# Power_Supply.net
KiCad netlist of a schematic drawn in Altium Designer
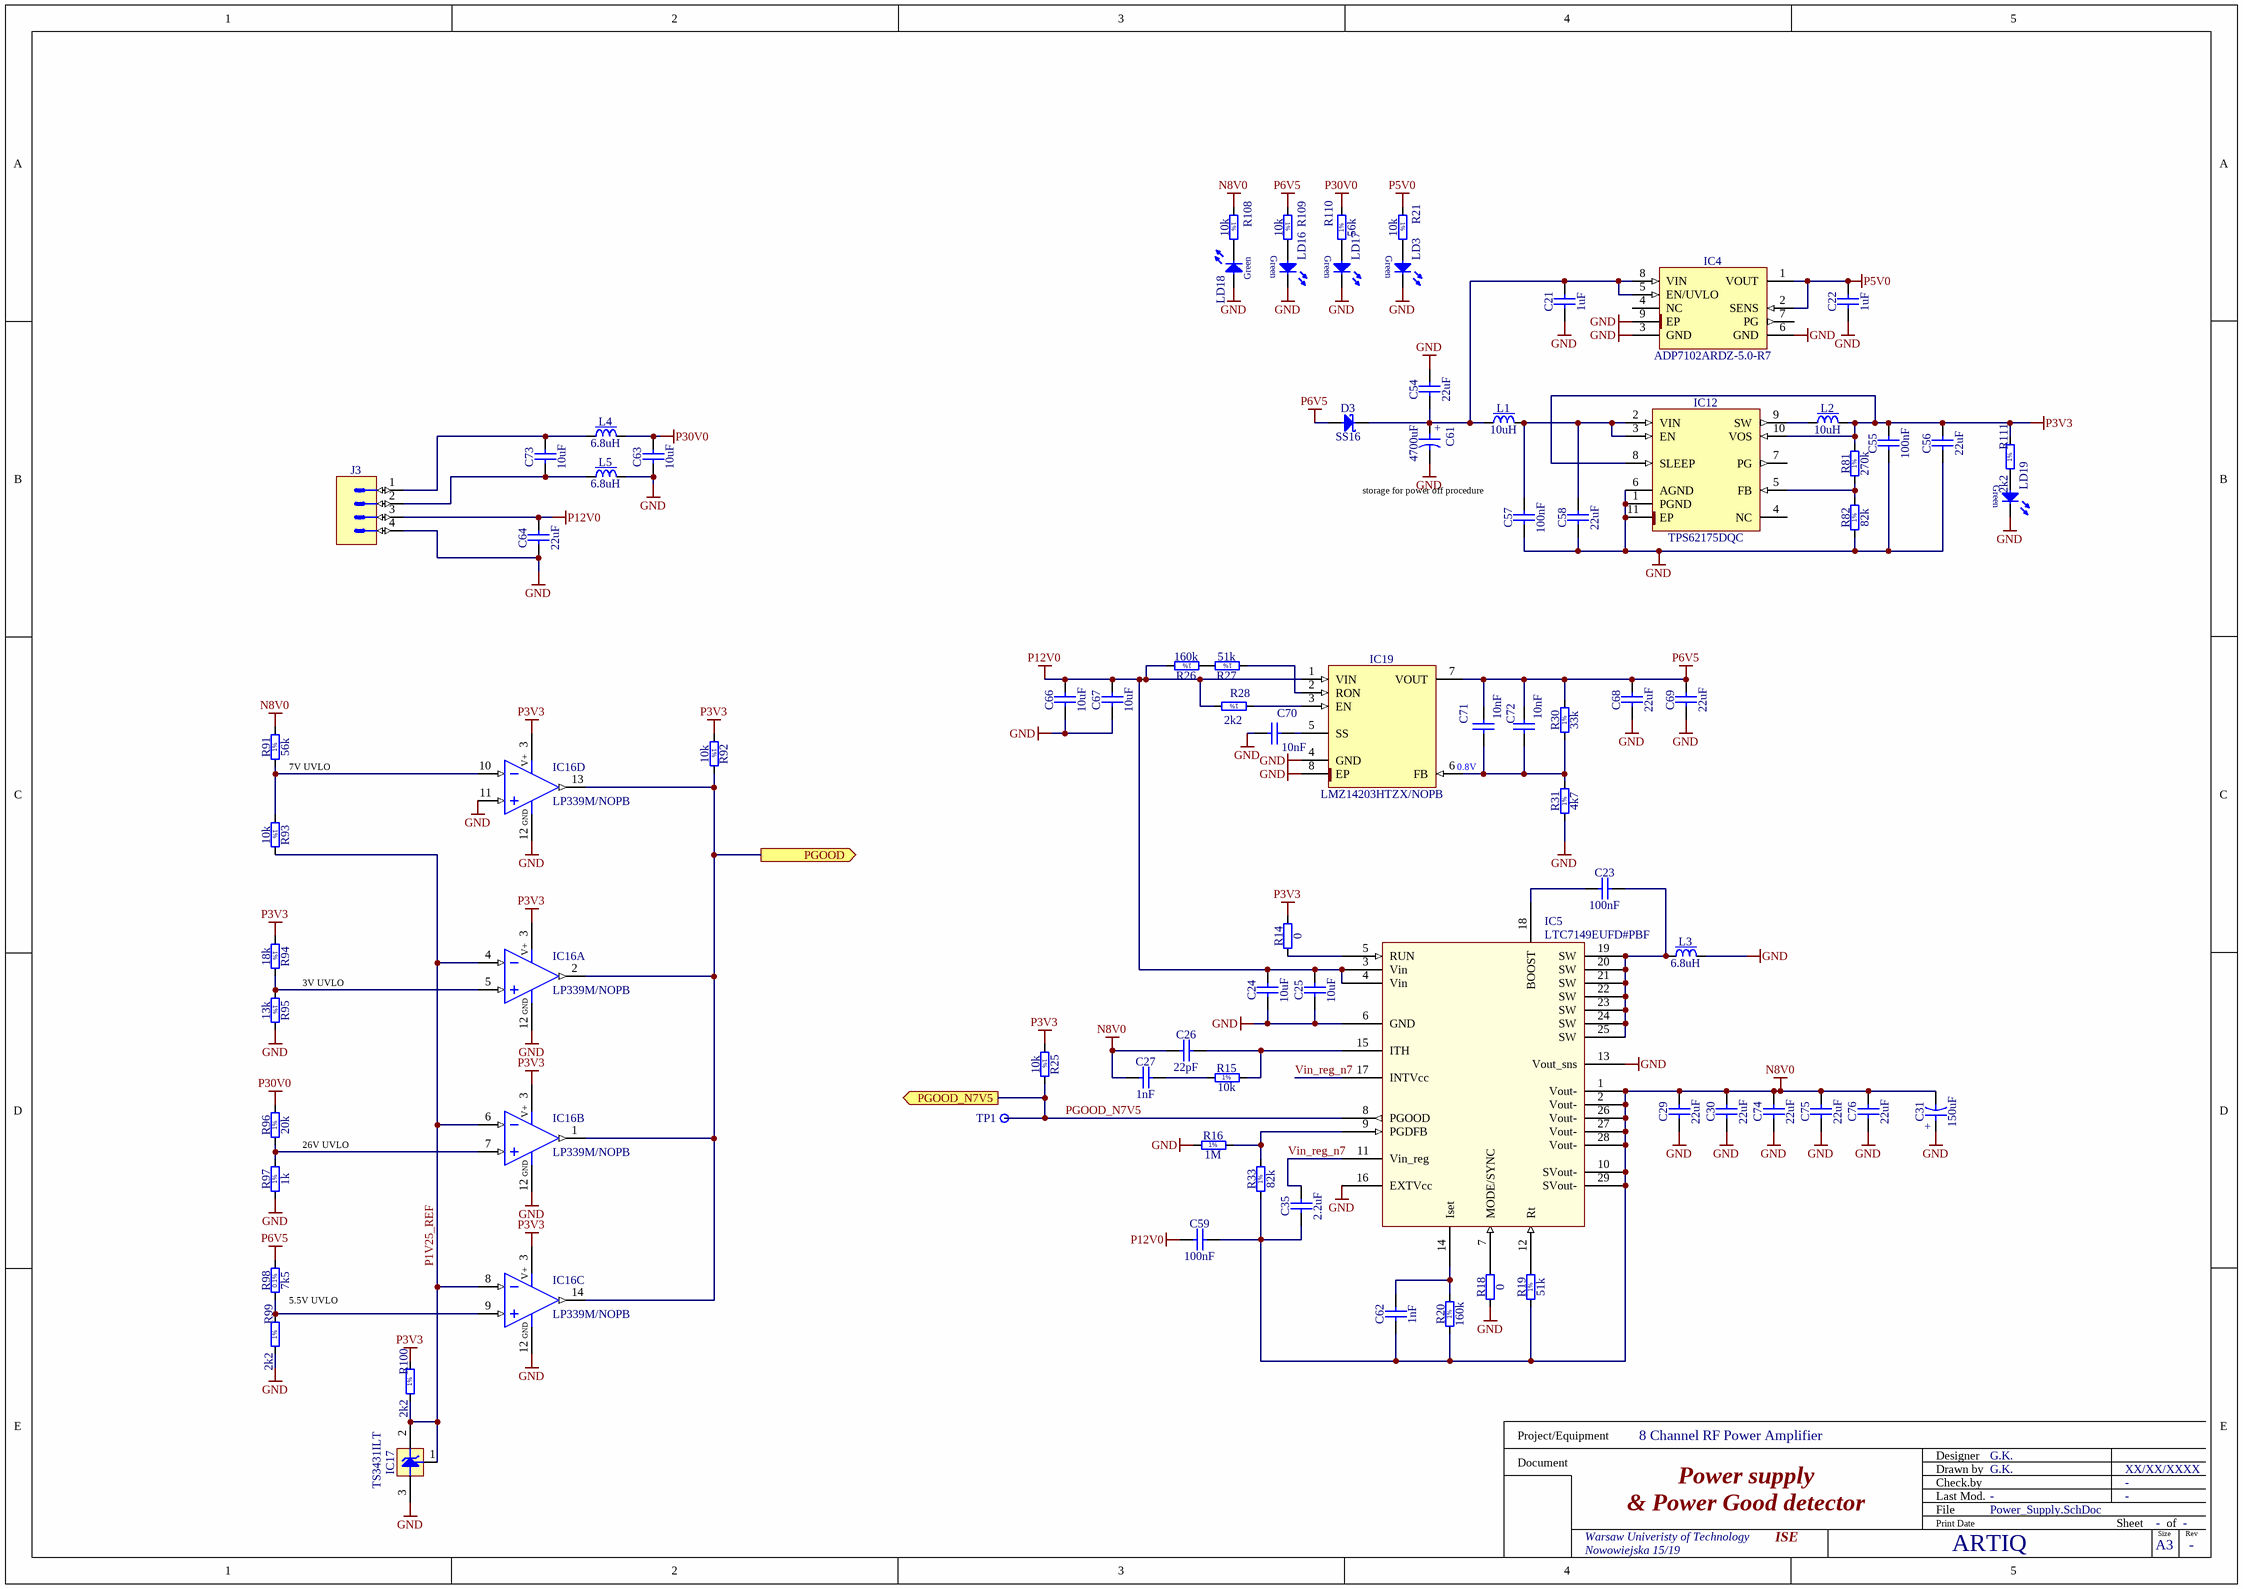
[diagram p0: Power_Supply.SchDoc]

(export (version "E")
  (design (tool "Eeschema 10.0.6"))
  (components
    (comp (ref "C21")
      (value "1uF")
      (footprint "CAPC2012X140N")
      (description "Non-polarised capacitor")
      (fields
        (field (name "PART NUMBER") "CC0805_1UF_35V_20%_X7R")
        (field (name "VOLTAGE") "35V")
        (field (name "AUTHOR") "CERN DEM JLC")
      )
      (libsource (lib "Capacitors") (part "Capacitor - non polarized"))
    )
    (comp (ref "C22")
      (value "1uF")
      (footprint "CAPC2012X140N")
      (description "Non-polarised capacitor")
      (fields
        (field (name "PART NUMBER") "CC0805_1UF_35V_20%_X7R")
        (field (name "VOLTAGE") "35V")
        (field (name "AUTHOR") "CERN DEM JLC")
      )
      (libsource (lib "Capacitors") (part "Capacitor - non polarized"))
    )
    (comp (ref "C23")
      (value "100nF")
      (footprint "CAPC1005X55N")
      (description "Non-polarised capacitor")
      (fields
        (field (name "PART NUMBER") "CC0402_100NF_16V_10%_X7R")
        (field (name "VOLTAGE") "16V")
        (field (name "AUTHOR") "CERN DEM JLC")
      )
      (libsource (lib "Capacitors") (part "Capacitor - non polarized"))
    )
    (comp (ref "C24")
      (value "10uF")
      (footprint "CAPC3216X190N")
      (description "Non-polarised capacitor")
      (fields
        (field (name "PART NUMBER") "CC1206_10UF_50V_10%_X5R_TDK_CGA5L3X5R1H106K160AB")
        (field (name "VOLTAGE") "50V")
        (field (name "AUTHOR") "CERN DEM BC")
      )
      (libsource (lib "Capacitors") (part "Capacitor - non polarized"))
    )
    (comp (ref "C25")
      (value "10uF")
      (footprint "CAPC3216X190N")
      (description "Non-polarised capacitor")
      (fields
        (field (name "PART NUMBER") "CC1206_10UF_50V_10%_X5R_TDK_CGA5L3X5R1H106K160AB")
        (field (name "VOLTAGE") "50V")
        (field (name "AUTHOR") "CERN DEM BC")
      )
      (libsource (lib "Capacitors") (part "Capacitor - non polarized"))
    )
    (comp (ref "C26")
      (value "22pF")
      (footprint "CAPC1005X55N")
      (description "Non-polarised capacitor")
      (fields
        (field (name "PART NUMBER") "CC0402_22PF_50V_5%_C0G")
        (field (name "VOLTAGE") "50V")
        (field (name "AUTHOR") "CERN DEM JLC")
      )
      (libsource (lib "Capacitors") (part "Capacitor - non polarized"))
    )
    (comp (ref "C27")
      (value "1nF")
      (footprint "CAPC1005X55N")
      (description "Non-polarised capacitor")
      (fields
        (field (name "PART NUMBER") "CC0402_1NF_50V_10%_X7R")
        (field (name "VOLTAGE") "50V")
        (field (name "AUTHOR") "CERN DEM JLC")
      )
      (libsource (lib "Capacitors") (part "Capacitor - non polarized"))
    )
    (comp (ref "C29")
      (value "22uF")
      (footprint "CAPC3216X180N")
      (description "Non-polarised capacitor")
      (fields
        (field (name "PART NUMBER") "CC1206_22UF_10V_10%_X7R")
        (field (name "VOLTAGE") "10V")
        (field (name "AUTHOR") "CERN DEM JLC")
      )
      (libsource (lib "Capacitors") (part "Capacitor - non polarized"))
    )
    (comp (ref "C30")
      (value "22uF")
      (footprint "CAPC3216X180N")
      (description "Non-polarised capacitor")
      (fields
        (field (name "PART NUMBER") "CC1206_22UF_10V_10%_X7R")
        (field (name "VOLTAGE") "10V")
        (field (name "AUTHOR") "CERN DEM JLC")
      )
      (libsource (lib "Capacitors") (part "Capacitor - non polarized"))
    )
    (comp (ref "C31")
      (value "150uF")
      (footprint "CAPMP7343X310N")
      (description "Polarised capacitor")
      (fields
        (field (name "PART NUMBER") "CTE7343-31_150UF_16V_10%_LESR0100")
        (field (name "VOLTAGE") "16V")
        (field (name "AUTHOR") "CERN DEM JLC")
      )
      (libsource (lib "Capacitors") (part "Capacitor - polarized"))
    )
    (comp (ref "C35")
      (value "2.2uF")
      (footprint "CAPC1608X87N")
      (description "Non-polarised capacitor")
      (fields
        (field (name "PART NUMBER") "CC0603_2.2UF_16V_10%_X5R")
        (field (name "VOLTAGE") "16V")
        (field (name "AUTHOR") "CERN DEM JLC")
      )
      (libsource (lib "Capacitors") (part "Capacitor - non polarized"))
    )
    (comp (ref "C54")
      (value "22uF")
      (footprint "CAPC2012X135N")
      (description "Non-polarised capacitor")
      (fields
        (field (name "PART NUMBER") "CC0805_22UF_16V_10%_X5R")
        (field (name "VOLTAGE") "16V")
        (field (name "AUTHOR") "CERN DEM JLC")
      )
      (libsource (lib "Capacitors") (part "Capacitor - non polarized"))
    )
    (comp (ref "C55")
      (value "100nF")
      (footprint "CAPC1005X55N")
      (description "Non-polarised capacitor")
      (fields
        (field (name "PART NUMBER") "CC0402_100NF_16V_10%_X5R")
        (field (name "VOLTAGE") "16V")
        (field (name "AUTHOR") "CERN DEM JLC")
      )
      (libsource (lib "Capacitors") (part "Capacitor - non polarized"))
    )
    (comp (ref "C56")
      (value "22uF")
      (footprint "CAPC2012X135N")
      (description "Non-polarised capacitor")
      (fields
        (field (name "PART NUMBER") "CC0805_22UF_16V_10%_X5R")
        (field (name "VOLTAGE") "16V")
        (field (name "AUTHOR") "CERN DEM JLC")
      )
      (libsource (lib "Capacitors") (part "Capacitor - non polarized"))
    )
    (comp (ref "C57")
      (value "100nF")
      (footprint "CAPC1005X55N")
      (description "Non-polarised capacitor")
      (fields
        (field (name "PART NUMBER") "CC0402_100NF_16V_10%_X5R")
        (field (name "VOLTAGE") "16V")
        (field (name "AUTHOR") "CERN DEM JLC")
      )
      (libsource (lib "Capacitors") (part "Capacitor - non polarized"))
    )
    (comp (ref "C58")
      (value "22uF")
      (footprint "CAPC2012X135N")
      (description "Non-polarised capacitor")
      (fields
        (field (name "PART NUMBER") "CC0805_22UF_16V_10%_X5R")
        (field (name "VOLTAGE") "16V")
        (field (name "AUTHOR") "CERN DEM JLC")
      )
      (libsource (lib "Capacitors") (part "Capacitor - non polarized"))
    )
    (comp (ref "C59")
      (value "100nF")
      (footprint "CAPC1608X87N")
      (description "Non-polarised capacitor")
      (fields
        (field (name "PART NUMBER") "CC0603_100NF_50V_10%_X5R")
        (field (name "VOLTAGE") "50V")
        (field (name "AUTHOR") "CERN DEM MR")
      )
      (libsource (lib "Capacitors") (part "Capacitor - non polarized"))
    )
    (comp (ref "C61")
      (value "4700uF")
      (footprint "CAPAE1900X1680N")
      (description "Polarised capacitor")
      (fields
        (field (name "PART NUMBER") "CAE1900-1680_4700UF_16V_20%")
        (field (name "VOLTAGE") "16V")
        (field (name "AUTHOR") "CERN DEM JLC")
      )
      (libsource (lib "Capacitors") (part "Capacitor - polarized"))
    )
    (comp (ref "C62")
      (value "1nF")
      (footprint "CAPC1005X55N")
      (description "Non-polarised capacitor")
      (fields
        (field (name "PART NUMBER") "CC0402_1NF_50V_10%_X7R")
        (field (name "VOLTAGE") "50V")
        (field (name "AUTHOR") "CERN DEM JLC")
      )
      (libsource (lib "Capacitors") (part "Capacitor - non polarized"))
    )
    (comp (ref "C63")
      (value "10uF")
      (footprint "CAPC3216X190N")
      (description "Non-polarised capacitor")
      (fields
        (field (name "PART NUMBER") "CC1206_10UF_50V_10%_X5R_TDK_CGA5L3X5R1H106K160AB")
        (field (name "VOLTAGE") "50V")
        (field (name "AUTHOR") "CERN DEM BC")
      )
      (libsource (lib "Capacitors") (part "Capacitor - non polarized"))
    )
    (comp (ref "C64")
      (value "22uF")
      (footprint "CAPC2012X135N")
      (description "Non-polarised capacitor")
      (fields
        (field (name "PART NUMBER") "CC0805_22UF_16V_10%_X5R")
        (field (name "VOLTAGE") "16V")
        (field (name "AUTHOR") "CERN DEM JLC")
      )
      (libsource (lib "Capacitors") (part "Capacitor - non polarized"))
    )
    (comp (ref "C66")
      (value "10uF")
      (footprint "CAPC3216X190N")
      (description "Non-polarised capacitor")
      (fields
        (field (name "PART NUMBER") "CC1206_10UF_50V_10%_X5R_TDK_CGA5L3X5R1H106K160AB")
        (field (name "VOLTAGE") "50V")
        (field (name "AUTHOR") "CERN DEM BC")
      )
      (libsource (lib "Capacitors") (part "Capacitor - non polarized"))
    )
    (comp (ref "C67")
      (value "10uF")
      (footprint "CAPC3216X190N")
      (description "Non-polarised capacitor")
      (fields
        (field (name "PART NUMBER") "CC1206_10UF_50V_10%_X5R_TDK_CGA5L3X5R1H106K160AB")
        (field (name "VOLTAGE") "50V")
        (field (name "AUTHOR") "CERN DEM BC")
      )
      (libsource (lib "Capacitors") (part "Capacitor - non polarized"))
    )
    (comp (ref "C68")
      (value "22uF")
      (footprint "CAPC2012X135N")
      (description "Non-polarised capacitor")
      (fields
        (field (name "PART NUMBER") "CC0805_22UF_16V_10%_X5R")
        (field (name "VOLTAGE") "16V")
        (field (name "AUTHOR") "CERN DEM JLC")
      )
      (libsource (lib "Capacitors") (part "Capacitor - non polarized"))
    )
    (comp (ref "C69")
      (value "22uF")
      (footprint "CAPC2012X135N")
      (description "Non-polarised capacitor")
      (fields
        (field (name "PART NUMBER") "CC0805_22UF_16V_10%_X5R")
        (field (name "VOLTAGE") "16V")
        (field (name "AUTHOR") "CERN DEM JLC")
      )
      (libsource (lib "Capacitors") (part "Capacitor - non polarized"))
    )
    (comp (ref "C70")
      (value "10nF")
      (footprint "CAPC1608X87N")
      (description "Non-polarised capacitor")
      (fields
        (field (name "PART NUMBER") "CC0603_10NF_50V_5%_C0G")
        (field (name "VOLTAGE") "50V")
        (field (name "AUTHOR") "CERN DEM JLC")
      )
      (libsource (lib "Capacitors") (part "Capacitor - non polarized"))
    )
    (comp (ref "C71")
      (value "10nF")
      (footprint "CAPC1608X87N")
      (description "Non-polarised capacitor")
      (fields
        (field (name "PART NUMBER") "CC0603_10NF_50V_5%_C0G")
        (field (name "VOLTAGE") "50V")
        (field (name "AUTHOR") "CERN DEM JLC")
      )
      (libsource (lib "Capacitors") (part "Capacitor - non polarized"))
    )
    (comp (ref "C72")
      (value "10nF")
      (footprint "CAPC1608X87N")
      (description "Non-polarised capacitor")
      (fields
        (field (name "PART NUMBER") "CC0603_10NF_50V_5%_C0G")
        (field (name "VOLTAGE") "50V")
        (field (name "AUTHOR") "CERN DEM JLC")
      )
      (libsource (lib "Capacitors") (part "Capacitor - non polarized"))
    )
    (comp (ref "C73")
      (value "10uF")
      (footprint "CAPC3216X190N")
      (description "Non-polarised capacitor")
      (fields
        (field (name "PART NUMBER") "CC1206_10UF_50V_10%_X5R_TDK_CGA5L3X5R1H106K160AB")
        (field (name "VOLTAGE") "50V")
        (field (name "AUTHOR") "CERN DEM BC")
      )
      (libsource (lib "Capacitors") (part "Capacitor - non polarized"))
    )
    (comp (ref "C74")
      (value "22uF")
      (footprint "CAPC3216X180N")
      (description "Non-polarised capacitor")
      (fields
        (field (name "PART NUMBER") "CC1206_22UF_10V_10%_X7R")
        (field (name "VOLTAGE") "10V")
        (field (name "AUTHOR") "CERN DEM JLC")
      )
      (libsource (lib "Capacitors") (part "Capacitor - non polarized"))
    )
    (comp (ref "C75")
      (value "22uF")
      (footprint "CAPC3216X180N")
      (description "Non-polarised capacitor")
      (fields
        (field (name "PART NUMBER") "CC1206_22UF_10V_10%_X7R")
        (field (name "VOLTAGE") "10V")
        (field (name "AUTHOR") "CERN DEM JLC")
      )
      (libsource (lib "Capacitors") (part "Capacitor - non polarized"))
    )
    (comp (ref "C76")
      (value "22uF")
      (footprint "CAPC3216X180N")
      (description "Non-polarised capacitor")
      (fields
        (field (name "PART NUMBER") "CC1206_22UF_10V_10%_X7R")
        (field (name "VOLTAGE") "10V")
        (field (name "AUTHOR") "CERN DEM JLC")
      )
      (libsource (lib "Capacitors") (part "Capacitor - non polarized"))
    )
    (comp (ref "D3")
      (value "SS16")
      (footprint "DIOM5127X229N")
      (description "Schottky Diode")
      (fields
        (field (name "VOLTAGE") "60V")
        (field (name "POWER") "1A")
        (field (name "AUTHOR") "CERN DEM JLC")
      )
      (libsource (lib "ICs And Semiconductors") (part "Diode Schottky"))
    )
    (comp (ref "IC4")
      (value "ADP7102ARDZ-5.0-R7")
      (footprint "SOIC127P600X175-9N-R241X309")
      (description "300 mA, Low Noise, CMOS LDO Linear Regulator")
      (fields (field (name "MANUFACTURER") "ANALOG DEVICES") (field (name "AUTHOR") "CERN DEM JLC"))
      (libsource (lib "ICs And Semiconductors") (part "ADP7102ARDZ-X.X-R7"))
    )
    (comp (ref "IC5")
      (value "LTC7149EUFD#PBF")
      (footprint "QFN50P400X500X80_HS-29N")
      (description "LTC7149 - 60V, 4A Synchronous Step-Down Regulator for Inverting Outputs")
      (fields (field (name "MANUFACTURER") "Linear technology"))
      (libsource (lib "misc") (part "LTC7149EUFD#PBF"))
    )
    (comp (ref "IC12")
      (value "TPS62175DQC")
      (footprint "SON50P200X300X80-11N-R94X250")
      (description "4.75-28VDC to 1-6VDC, 500mA Step-Down Converter With Sleep Mode")
      (fields (field (name "MANUFACTURER") "TEXAS INSTRUMENTS") (field (name "AUTHOR") "CERN DEM JMW"))
      (libsource (lib "ICs And Semiconductors") (part "TPS62175"))
    )
    (comp (ref "IC16")
      (value "LP339M/NOPB")
      (footprint "SOIC127P600X175-14N")
      (description "Quad Operational Amplifier")
      (fields (field (name "MANUFACTURER") "TEXAS INSTRUMENTS") (field (name "AUTHOR") "CERN DEM MR"))
      (libsource (lib "ICs And Semiconductors") (part "Operational Amplifier x4 Type5"))
    )
    (comp (ref "IC17")
      (value "TS3431ILT")
      (footprint "SOT95P237X112-3N")
      (description "Precision Reference 1=Adj 2=Cathode 3=Anode")
      (fields (field (name "MANUFACTURER") "ST MICROELECTRONICS") (field (name "AUTHOR") "CERN DEM JLC"))
      (libsource (lib "ICs And Semiconductors") (part "VREF 1ADJ-2C-3A"))
    )
    (comp (ref "IC19")
      (value "LMZ14203HTZX/NOPB")
      (footprint "TEXAS_TO-PMOD (NDW)")
      (description "3A SIMPLE SWITCHER® Power Module with 42V Maximum Input Voltage")
      (fields (field (name "MANUFACTURER") "TEXAS INSTRUMENTS") (field (name "AUTHOR") "GK"))
      (libsource (lib "LIBRARY_SCH") (part "PM_LMZ14203"))
    )
    (comp (ref "J3")
      (value "~")
      (footprint "PHOENIX_1755752")
      (description "Connector 4 Male")
      (fields
        (field (name "PART NUMBER") "PHOENIX_1755752")
        (field (name "MANUFACTURER") "PHOENIX CONTACT")
        (field (name "AUTHOR") "CERN DEM JLC")
      )
      (libsource (lib "Connectors") (part "Connector 4 Male"))
    )
    (comp (ref "L1")
      (value "10uH")
      (footprint "IND_MURATA-PS_8400")
      (description "Inductor With Core")
      (fields
        (field (name "PART NUMBER") "IND_10UH_10%_MURATA-PS_8400")
        (field (name "POWER") "950mA")
        (field (name "AUTHOR") "CERN DEM JLC")
      )
      (libsource (lib "Inductors & Transformers") (part "Inductor With Magnetic core"))
    )
    (comp (ref "L2")
      (value "10uH")
      (footprint "IND_MURATA-PS_8400")
      (description "Inductor With Core")
      (fields
        (field (name "PART NUMBER") "IND_10UH_10%_MURATA-PS_8400")
        (field (name "POWER") "950mA")
        (field (name "AUTHOR") "CERN DEM JLC")
      )
      (libsource (lib "Inductors & Transformers") (part "Inductor With Magnetic core"))
    )
    (comp (ref "L3")
      (value "6.8uH")
      (footprint "INDM6965X300N")
      (description "Inductor With Core")
      (fields
        (field (name "PART NUMBER") "IND2525_1.5UH_20%_VISHAY_IHLP-2525CZ")
        (field (name "POWER") "9A")
        (field (name "AUTHOR") "CERN DEM JLC")
      )
      (libsource (lib "Inductors & Transformers") (part "Inductor With Magnetic core"))
    )
    (comp (ref "L4")
      (value "6.8uH")
      (footprint "INDM6965X300N")
      (description "Inductor With Core")
      (fields
        (field (name "PART NUMBER") "IND2525_1.5UH_20%_VISHAY_IHLP-2525CZ")
        (field (name "POWER") "9A")
        (field (name "AUTHOR") "CERN DEM JLC")
      )
      (libsource (lib "Inductors & Transformers") (part "Inductor With Magnetic core"))
    )
    (comp (ref "L5")
      (value "6.8uH")
      (footprint "INDM6965X300N")
      (description "Inductor With Core")
      (fields
        (field (name "PART NUMBER") "IND2525_1.5UH_20%_VISHAY_IHLP-2525CZ")
        (field (name "POWER") "9A")
        (field (name "AUTHOR") "CERN DEM JLC")
      )
      (libsource (lib "Inductors & Transformers") (part "Inductor With Magnetic core"))
    )
    (comp (ref "LD3")
      (value "Green")
      (footprint "LED_KINGBRIGHT_KPH-1608CGCK")
      (description "LED Green 1C 2A")
      (fields
        (field (name "PART NUMBER") "LED_KINGBRIGHT_KPH-1608CGCK")
        (field (name "MANUFACTURER") "KINGBRIGHT")
        (field (name "AUTHOR") "CERN DEM JLC")
      )
      (libsource (lib "ICs And Semiconductors") (part "LED Green 1C 2A"))
    )
    (comp (ref "LD16")
      (value "Green")
      (footprint "LED_KINGBRIGHT_KPH-1608CGCK")
      (description "LED Green 1C 2A")
      (fields
        (field (name "PART NUMBER") "LED_KINGBRIGHT_KPH-1608CGCK")
        (field (name "MANUFACTURER") "KINGBRIGHT")
        (field (name "AUTHOR") "CERN DEM JLC")
      )
      (libsource (lib "ICs And Semiconductors") (part "LED Green 1C 2A"))
    )
    (comp (ref "LD17")
      (value "Green")
      (footprint "LED_KINGBRIGHT_KPH-1608CGCK")
      (description "LED Green 1C 2A")
      (fields
        (field (name "PART NUMBER") "LED_KINGBRIGHT_KPH-1608CGCK")
        (field (name "MANUFACTURER") "KINGBRIGHT")
        (field (name "AUTHOR") "CERN DEM JLC")
      )
      (libsource (lib "ICs And Semiconductors") (part "LED Green 1C 2A"))
    )
    (comp (ref "LD18")
      (value "Green")
      (footprint "LED_KINGBRIGHT_KPH-1608CGCK")
      (description "LED Green 1C 2A")
      (fields
        (field (name "PART NUMBER") "LED_KINGBRIGHT_KPH-1608CGCK")
        (field (name "MANUFACTURER") "KINGBRIGHT")
        (field (name "AUTHOR") "CERN DEM JLC")
      )
      (libsource (lib "ICs And Semiconductors") (part "LED Green 1C 2A"))
    )
    (comp (ref "LD19")
      (value "Green")
      (footprint "LED_OSRAM_LGL29K")
      (description "LED Green 1C 2A")
      (fields
        (field (name "PART NUMBER") "LED_OSRAM_LG L29K-G2J1-24-Z")
        (field (name "MANUFACTURER") "OSRAM")
        (field (name "AUTHOR") "CERN DEM JLC")
      )
      (libsource (lib "ICs And Semiconductors") (part "LED Green 1C 2A"))
    )
    (comp (ref "R14")
      (value "0")
      (footprint "RESC1005X40N")
      (description "Resistor")
      (fields
        (field (name "PART NUMBER") "R0402_0R_JUMPER")
        (field (name "MANUFACTURER") "GENERIC")
        (field (name "AUTHOR") "CERN DEM JLC")
      )
      (libsource (lib "Resistors") (part "Resistor"))
    )
    (comp (ref "R15")
      (value "10k")
      (footprint "RESC1005X40N")
      (description "Resistor - 1%")
      (fields
        (field (name "PART NUMBER") "R0402_10K_1%_0.0625W_100PPM")
        (field (name "POWER") "0.0625W")
        (field (name "AUTHOR") "CERN DEM JLC")
      )
      (libsource (lib "Resistors") (part "Resistor - 1%"))
    )
    (comp (ref "R16")
      (value "1M")
      (footprint "RESC1005X40N")
      (description "Resistor - 1%")
      (fields
        (field (name "PART NUMBER") "R0402_1M_1%_0.0625W_100PPM")
        (field (name "POWER") "0.0625W")
        (field (name "AUTHOR") "CERN DEM JLC")
      )
      (libsource (lib "Resistors") (part "Resistor - 1%"))
    )
    (comp (ref "R18")
      (value "0")
      (footprint "RESC1005X40N")
      (description "Resistor")
      (fields
        (field (name "PART NUMBER") "R0402_0R_JUMPER")
        (field (name "MANUFACTURER") "GENERIC")
        (field (name "AUTHOR") "CERN DEM JLC")
      )
      (libsource (lib "Resistors") (part "Resistor"))
    )
    (comp (ref "R19")
      (value "51k")
      (footprint "RESC1005X40N")
      (description "Resistor - 1%")
      (fields
        (field (name "PART NUMBER") "R0402_51K_1%_0.0625W_100PPM")
        (field (name "POWER") "0.0625W")
        (field (name "AUTHOR") "CERN DEM JLC")
      )
      (libsource (lib "Resistors") (part "Resistor - 1%"))
    )
    (comp (ref "R20")
      (value "160k")
      (footprint "RESC1005X40N")
      (description "Resistor - 1%")
      (fields
        (field (name "PART NUMBER") "R0402_160K_1%_0.0625W_100PPM")
        (field (name "POWER") "0.0625W")
        (field (name "AUTHOR") "CERN DEM JLC")
      )
      (libsource (lib "Resistors") (part "Resistor - 1%"))
    )
    (comp (ref "R21")
      (value "10k")
      (footprint "RESC1005X40N")
      (description "Resistor - 1%")
      (fields
        (field (name "PART NUMBER") "R0402_10K_1%_0.0625W_100PPM")
        (field (name "POWER") "0.0625W")
        (field (name "AUTHOR") "CERN DEM JLC")
      )
      (libsource (lib "Resistors") (part "Resistor - 1%"))
    )
    (comp (ref "R25")
      (value "10k")
      (footprint "RESC1005X40N")
      (description "Resistor - 1%")
      (fields
        (field (name "PART NUMBER") "R0402_10K_1%_0.0625W_100PPM")
        (field (name "POWER") "0.0625W")
        (field (name "AUTHOR") "CERN DEM JLC")
      )
      (libsource (lib "Resistors") (part "Resistor - 1%"))
    )
    (comp (ref "R26")
      (value "160k")
      (footprint "RESC1005X40N")
      (description "Resistor - 1%")
      (fields
        (field (name "PART NUMBER") "R0402_160K_1%_0.0625W_100PPM")
        (field (name "POWER") "0.0625W")
        (field (name "AUTHOR") "CERN DEM JLC")
      )
      (libsource (lib "Resistors") (part "Resistor - 1%"))
    )
    (comp (ref "R27")
      (value "51k")
      (footprint "RESC1005X40N")
      (description "Resistor - 1%")
      (fields
        (field (name "PART NUMBER") "R0402_51K_1%_0.0625W_100PPM")
        (field (name "POWER") "0.0625W")
        (field (name "AUTHOR") "CERN DEM JLC")
      )
      (libsource (lib "Resistors") (part "Resistor - 1%"))
    )
    (comp (ref "R28")
      (value "2k2")
      (footprint "RESC1005X40N")
      (description "Resistor - 1%")
      (fields
        (field (name "PART NUMBER") "R0402_2K2_1%_0.0625W_100PPM")
        (field (name "POWER") "0.0625W")
        (field (name "AUTHOR") "CERN DEM JLC")
      )
      (libsource (lib "Resistors") (part "Resistor - 1%"))
    )
    (comp (ref "R30")
      (value "33k")
      (footprint "RESC1608X55N")
      (description "Resistor - 1%")
      (fields
        (field (name "PART NUMBER") "R0603_33K_1%_0.1W_100PPM")
        (field (name "POWER") "0.1W")
        (field (name "AUTHOR") "CERN DEM JLC")
      )
      (libsource (lib "Resistors") (part "Resistor - 1%"))
    )
    (comp (ref "R31")
      (value "4k7")
      (footprint "RESC1608X55N")
      (description "Resistor - 1%")
      (fields
        (field (name "PART NUMBER") "R0603_4K7_1%_0.1W_100PPM")
        (field (name "POWER") "0.1W")
        (field (name "AUTHOR") "CERN DEM JLC")
      )
      (libsource (lib "Resistors") (part "Resistor - 1%"))
    )
    (comp (ref "R33")
      (value "82k")
      (footprint "RESC1608X55N")
      (description "Resistor - 1%")
      (fields
        (field (name "PART NUMBER") "R0603_82K_1%_0.1W_100PPM")
        (field (name "POWER") "0.1W")
        (field (name "AUTHOR") "CERN DEM JLC")
      )
      (libsource (lib "Resistors") (part "Resistor - 1%"))
    )
    (comp (ref "R81")
      (value "270k")
      (footprint "RESC1608X55N")
      (description "Resistor - 1%")
      (fields
        (field (name "PART NUMBER") "R0603_270K_1%_0.1W_100PPM")
        (field (name "POWER") "0.1W")
        (field (name "AUTHOR") "CERN DEM JLC")
      )
      (libsource (lib "Resistors") (part "Resistor - 1%"))
    )
    (comp (ref "R82")
      (value "82k")
      (footprint "RESC1608X55N")
      (description "Resistor - 1%")
      (fields
        (field (name "PART NUMBER") "R0603_82K_1%_0.1W_100PPM")
        (field (name "POWER") "0.1W")
        (field (name "AUTHOR") "CERN DEM JLC")
      )
      (libsource (lib "Resistors") (part "Resistor - 1%"))
    )
    (comp (ref "R91")
      (value "56k")
      (footprint "RESC1608X55N")
      (description "Resistor - 1%")
      (fields
        (field (name "PART NUMBER") "R0603_56K_1%_0.1W_100PPM")
        (field (name "POWER") "0.1W")
        (field (name "AUTHOR") "CERN DEM JLC")
      )
      (libsource (lib "Resistors") (part "Resistor - 1%"))
    )
    (comp (ref "R92")
      (value "10k")
      (footprint "RESC1005X40N")
      (description "Resistor - 1%")
      (fields
        (field (name "PART NUMBER") "R0402_10K_1%_0.0625W_100PPM")
        (field (name "POWER") "0.0625W")
        (field (name "AUTHOR") "CERN DEM JLC")
      )
      (libsource (lib "Resistors") (part "Resistor - 1%"))
    )
    (comp (ref "R93")
      (value "10k")
      (footprint "RESC1005X40N")
      (description "Resistor - 1%")
      (fields
        (field (name "PART NUMBER") "R0402_10K_1%_0.0625W_100PPM")
        (field (name "POWER") "0.0625W")
        (field (name "AUTHOR") "CERN DEM JLC")
      )
      (libsource (lib "Resistors") (part "Resistor - 1%"))
    )
    (comp (ref "R94")
      (value "18k")
      (footprint "RESC1608X55N")
      (description "Resistor - 1%")
      (fields
        (field (name "PART NUMBER") "R0603_18K_1%_0.1W_100PPM")
        (field (name "POWER") "0.1W")
        (field (name "AUTHOR") "CERN DEM JLC")
      )
      (libsource (lib "Resistors") (part "Resistor - 1%"))
    )
    (comp (ref "R95")
      (value "13k")
      (footprint "RESC1608X55N")
      (description "Resistor - 1%")
      (fields
        (field (name "PART NUMBER") "R0603_13K_1%_0.1W_100PPM")
        (field (name "POWER") "0.1W")
        (field (name "AUTHOR") "CERN DEM JLC")
      )
      (libsource (lib "Resistors") (part "Resistor - 1%"))
    )
    (comp (ref "R96")
      (value "20k")
      (footprint "RESC1608X55N")
      (description "Resistor - 1%")
      (fields
        (field (name "PART NUMBER") "R0603_20K_1%_0.1W_100PPM")
        (field (name "POWER") "0.1W")
        (field (name "AUTHOR") "CERN DEM JLC")
      )
      (libsource (lib "Resistors") (part "Resistor - 1%"))
    )
    (comp (ref "R97")
      (value "1k")
      (footprint "RESC1608X55N")
      (description "Resistor - 1%")
      (fields
        (field (name "PART NUMBER") "R0603_1K_1%_0.1W_100PPM")
        (field (name "POWER") "0.1W")
        (field (name "AUTHOR") "CERN DEM JLC")
      )
      (libsource (lib "Resistors") (part "Resistor - 1%"))
    )
    (comp (ref "R98")
      (value "7k5")
      (footprint "RESC1608X55N")
      (description "Resistor - 0.1%")
      (fields
        (field (name "PART NUMBER") "R0603_7K5_0.1%_0.063W_10PPM")
        (field (name "POWER") "0.063W")
        (field (name "AUTHOR") "CERN DEM JLC")
      )
      (libsource (lib "Resistors") (part "Resistor - 0.1%"))
    )
    (comp (ref "R99")
      (value "2k2")
      (footprint "RESC1005X40N")
      (description "Resistor - 1%")
      (fields
        (field (name "PART NUMBER") "R0402_2K2_1%_0.0625W_100PPM")
        (field (name "POWER") "0.0625W")
        (field (name "AUTHOR") "CERN DEM JLC")
      )
      (libsource (lib "Resistors") (part "Resistor - 1%"))
    )
    (comp (ref "R100")
      (value "2k2")
      (footprint "RESC1005X40N")
      (description "Resistor - 1%")
      (fields
        (field (name "PART NUMBER") "R0402_2K2_1%_0.0625W_100PPM")
        (field (name "POWER") "0.0625W")
        (field (name "AUTHOR") "CERN DEM JLC")
      )
      (libsource (lib "Resistors") (part "Resistor - 1%"))
    )
    (comp (ref "R108")
      (value "10k")
      (footprint "RESC1005X40N")
      (description "Resistor - 1%")
      (fields
        (field (name "PART NUMBER") "R0402_10K_1%_0.0625W_100PPM")
        (field (name "POWER") "0.0625W")
        (field (name "AUTHOR") "CERN DEM JLC")
      )
      (libsource (lib "Resistors") (part "Resistor - 1%"))
    )
    (comp (ref "R109")
      (value "10k")
      (footprint "RESC1005X40N")
      (description "Resistor - 1%")
      (fields
        (field (name "PART NUMBER") "R0402_10K_1%_0.0625W_100PPM")
        (field (name "POWER") "0.0625W")
        (field (name "AUTHOR") "CERN DEM JLC")
      )
      (libsource (lib "Resistors") (part "Resistor - 1%"))
    )
    (comp (ref "R110")
      (value "56k")
      (footprint "RESC1608X55N")
      (description "Resistor - 1%")
      (fields
        (field (name "PART NUMBER") "R0603_56K_1%_0.1W_100PPM")
        (field (name "POWER") "0.1W")
        (field (name "AUTHOR") "CERN DEM JLC")
      )
      (libsource (lib "Resistors") (part "Resistor - 1%"))
    )
    (comp (ref "R111")
      (value "2k2")
      (footprint "RESC1005X40N")
      (description "Resistor - 1%")
      (fields
        (field (name "PART NUMBER") "R0402_2K2_1%_0.0625W_100PPM")
        (field (name "POWER") "0.0625W")
        (field (name "AUTHOR") "CERN DEM JLC")
      )
      (libsource (lib "Resistors") (part "Resistor - 1%"))
    )
    (comp (ref "TP1")
      (value "Test Point")
      (footprint "TPS127")
      (fields (field (name "PART NUMBER") "SMD_PAD_1.27X1.27MM") (field (name "AUTHOR") "CERN DEM JLC"))
      (libsource (lib "Eletro-mechanical") (part "Test Point"))
    )
  )
  (nets
    (net (code "1") (name "/P1V25_REF") (class "Default")
      (node (ref "IC16") (pin "4") (pinfunction "IN-_4") (pintype "input"))
      (node (ref "IC16") (pin "6") (pinfunction "IN-_6") (pintype "input"))
      (node (ref "IC16") (pin "8") (pinfunction "IN-_8") (pintype "input"))
      (node (ref "IC17") (pin "1") (pinfunction "Adj_1") (pintype "passive"))
      (node (ref "IC17") (pin "2") (pinfunction "C_2") (pintype "passive"))
      (node (ref "R100") (pin "1") (pinfunction "1_1") (pintype "passive"))
      (node (ref "R93") (pin "2") (pinfunction "2_2") (pintype "passive"))
    )
    (net (code "2") (name "/PGOOD") (class "Default")
      (node (ref "IC16") (pin "1") (pinfunction "OUT_1") (pintype "output"))
      (node (ref "IC16") (pin "13") (pinfunction "OUT_13") (pintype "output"))
      (node (ref "IC16") (pin "14") (pinfunction "OUT_14") (pintype "output"))
      (node (ref "IC16") (pin "2") (pinfunction "OUT_2") (pintype "output"))
      (node (ref "R92") (pin "2") (pinfunction "2_2") (pintype "passive"))
    )
    (net (code "3") (name "/PGOOD_N7V5") (class "Default")
      (node (ref "IC5") (pin "8") (pinfunction "PGOOD_8") (pintype "output"))
      (node (ref "R25") (pin "2") (pinfunction "2_2") (pintype "passive"))
      (node (ref "TP1") (pin "1") (pinfunction "1_1") (pintype "bidirectional"))
    )
    (net (code "4") (name "/Vin_reg_n7") (class "Default")
      (node (ref "C35") (pin "2") (pinfunction "2_2") (pintype "passive"))
      (node (ref "IC5") (pin "11") (pinfunction "Vin_reg_11") (pintype "passive"))
      (node (ref "IC5") (pin "17") (pinfunction "INTVcc_17") (pintype "power_in"))
    )
    (net (code "5") (name "GND") (class "Default")
      (node (ref "C21") (pin "1") (pinfunction "1_1") (pintype "passive"))
      (node (ref "C22") (pin "1") (pinfunction "1_1") (pintype "passive"))
      (node (ref "C24") (pin "1") (pinfunction "1_1") (pintype "passive"))
      (node (ref "C25") (pin "1") (pinfunction "1_1") (pintype "passive"))
      (node (ref "C29") (pin "1") (pinfunction "1_1") (pintype "passive"))
      (node (ref "C30") (pin "1") (pinfunction "1_1") (pintype "passive"))
      (node (ref "C31") (pin "1") (pinfunction "1_1") (pintype "passive"))
      (node (ref "C54") (pin "2") (pinfunction "2_2") (pintype "passive"))
      (node (ref "C55") (pin "1") (pinfunction "1_1") (pintype "passive"))
      (node (ref "C56") (pin "1") (pinfunction "1_1") (pintype "passive"))
      (node (ref "C57") (pin "1") (pinfunction "1_1") (pintype "passive"))
      (node (ref "C58") (pin "1") (pinfunction "1_1") (pintype "passive"))
      (node (ref "C61") (pin "2") (pinfunction "2_2") (pintype "passive"))
      (node (ref "C63") (pin "1") (pinfunction "1_1") (pintype "passive"))
      (node (ref "C64") (pin "1") (pinfunction "1_1") (pintype "passive"))
      (node (ref "C66") (pin "1") (pinfunction "1_1") (pintype "passive"))
      (node (ref "C67") (pin "1") (pinfunction "1_1") (pintype "passive"))
      (node (ref "C68") (pin "1") (pinfunction "1_1") (pintype "passive"))
      (node (ref "C69") (pin "1") (pinfunction "1_1") (pintype "passive"))
      (node (ref "C70") (pin "1") (pinfunction "1_1") (pintype "passive"))
      (node (ref "C74") (pin "1") (pinfunction "1_1") (pintype "passive"))
      (node (ref "C75") (pin "1") (pinfunction "1_1") (pintype "passive"))
      (node (ref "C76") (pin "1") (pinfunction "1_1") (pintype "passive"))
      (node (ref "IC12") (pin "1") (pinfunction "PGND_1") (pintype "power_in"))
      (node (ref "IC12") (pin "11") (pinfunction "EP_11") (pintype "power_in"))
      (node (ref "IC12") (pin "6") (pinfunction "AGND_6") (pintype "power_in"))
      (node (ref "IC16") (pin "11") (pinfunction "IN+_11") (pintype "input"))
      (node (ref "IC16") (pin "12") (pinfunction "GND_12") (pintype "power_in"))
      (node (ref "IC17") (pin "3") (pinfunction "A_3") (pintype "passive"))
      (node (ref "IC19") (pin "4") (pinfunction "GND_4") (pintype "power_in"))
      (node (ref "IC19") (pin "8") (pinfunction "EP_8") (pintype "power_in"))
      (node (ref "IC4") (pin "3") (pinfunction "GND_3") (pintype "power_in"))
      (node (ref "IC4") (pin "6") (pinfunction "GND_6") (pintype "power_in"))
      (node (ref "IC4") (pin "9") (pinfunction "EP_9") (pintype "power_in"))
      (node (ref "IC5") (pin "13") (pinfunction "Vout_sns_13") (pintype "passive"))
      (node (ref "IC5") (pin "16") (pinfunction "EXTVcc_16") (pintype "power_in"))
      (node (ref "IC5") (pin "6") (pinfunction "GND_6") (pintype "power_in"))
      (node (ref "J3") (pin "4") (pinfunction "4_4") (pintype "bidirectional"))
      (node (ref "L3") (pin "2") (pinfunction "2_2") (pintype "passive"))
      (node (ref "L5") (pin "2") (pinfunction "2_2") (pintype "passive"))
      (node (ref "LD16") (pin "1") (pinfunction "C_1") (pintype "passive"))
      (node (ref "LD17") (pin "1") (pinfunction "C_1") (pintype "passive"))
      (node (ref "LD18") (pin "2") (pinfunction "A_2") (pintype "passive"))
      (node (ref "LD19") (pin "1") (pinfunction "C_1") (pintype "passive"))
      (node (ref "LD3") (pin "1") (pinfunction "C_1") (pintype "passive"))
      (node (ref "R16") (pin "1") (pinfunction "1_1") (pintype "passive"))
      (node (ref "R18") (pin "1") (pinfunction "1_1") (pintype "passive"))
      (node (ref "R31") (pin "1") (pinfunction "1_1") (pintype "passive"))
      (node (ref "R82") (pin "1") (pinfunction "1_1") (pintype "passive"))
      (node (ref "R95") (pin "2") (pinfunction "2_2") (pintype "passive"))
      (node (ref "R97") (pin "1") (pinfunction "1_1") (pintype "passive"))
      (node (ref "R99") (pin "1") (pinfunction "1_1") (pintype "passive"))
    )
    (net (code "6") (name "N8V0") (class "Default")
      (node (ref "C26") (pin "1") (pinfunction "1_1") (pintype "passive"))
      (node (ref "C27") (pin "1") (pinfunction "1_1") (pintype "passive"))
      (node (ref "C29") (pin "2") (pinfunction "2_2") (pintype "passive"))
      (node (ref "C30") (pin "2") (pinfunction "2_2") (pintype "passive"))
      (node (ref "C31") (pin "2") (pinfunction "2_2") (pintype "passive"))
      (node (ref "C35") (pin "1") (pinfunction "1_1") (pintype "passive"))
      (node (ref "C59") (pin "2") (pinfunction "2_2") (pintype "passive"))
      (node (ref "C62") (pin "1") (pinfunction "1_1") (pintype "passive"))
      (node (ref "C74") (pin "2") (pinfunction "2_2") (pintype "passive"))
      (node (ref "C75") (pin "2") (pinfunction "2_2") (pintype "passive"))
      (node (ref "C76") (pin "2") (pinfunction "2_2") (pintype "passive"))
      (node (ref "IC5") (pin "1") (pinfunction "Vout-_1") (pintype "power_in"))
      (node (ref "IC5") (pin "10") (pinfunction "SVout-_10") (pintype "power_in"))
      (node (ref "IC5") (pin "2") (pinfunction "Vout-_2") (pintype "power_in"))
      (node (ref "IC5") (pin "26") (pinfunction "Vout-_26") (pintype "power_in"))
      (node (ref "IC5") (pin "27") (pinfunction "Vout-_27") (pintype "power_in"))
      (node (ref "IC5") (pin "28") (pinfunction "Vout-_28") (pintype "power_in"))
      (node (ref "IC5") (pin "29") (pinfunction "SVout-_29") (pintype "power_in"))
      (node (ref "R108") (pin "1") (pinfunction "1_1") (pintype "passive"))
      (node (ref "R19") (pin "1") (pinfunction "1_1") (pintype "passive"))
      (node (ref "R20") (pin "1") (pinfunction "1_1") (pintype "passive"))
      (node (ref "R33") (pin "1") (pinfunction "1_1") (pintype "passive"))
      (node (ref "R91") (pin "2") (pinfunction "2_2") (pintype "passive"))
    )
    (net (code "7") (name "Net-(C23-Pad2)") (class "Default")
      (node (ref "C23") (pin "2") (pinfunction "2_2") (pintype "passive"))
      (node (ref "IC5") (pin "19") (pinfunction "SW_19") (pintype "power_in"))
      (node (ref "IC5") (pin "20") (pinfunction "SW_20") (pintype "power_in"))
      (node (ref "IC5") (pin "21") (pinfunction "SW_21") (pintype "power_in"))
      (node (ref "IC5") (pin "22") (pinfunction "SW_22") (pintype "power_in"))
      (node (ref "IC5") (pin "23") (pinfunction "SW_23") (pintype "power_in"))
      (node (ref "IC5") (pin "24") (pinfunction "SW_24") (pintype "power_in"))
      (node (ref "IC5") (pin "25") (pinfunction "SW_25") (pintype "power_in"))
      (node (ref "L3") (pin "1") (pinfunction "1_1") (pintype "passive"))
    )
    (net (code "8") (name "Net-(C27-Pad2)") (class "Default")
      (node (ref "C27") (pin "2") (pinfunction "2_2") (pintype "passive"))
      (node (ref "R15") (pin "1") (pinfunction "1_1") (pintype "passive"))
    )
    (net (code "9") (name "Net-(C73-Pad1)") (class "Default")
      (node (ref "C73") (pin "1") (pinfunction "1_1") (pintype "passive"))
      (node (ref "J3") (pin "2") (pinfunction "2_2") (pintype "bidirectional"))
      (node (ref "L5") (pin "1") (pinfunction "1_1") (pintype "passive"))
    )
    (net (code "10") (name "Net-(C73-Pad2)") (class "Default")
      (node (ref "C73") (pin "2") (pinfunction "2_2") (pintype "passive"))
      (node (ref "J3") (pin "1") (pinfunction "1_1") (pintype "bidirectional"))
      (node (ref "L4") (pin "1") (pinfunction "1_1") (pintype "passive"))
    )
    (net (code "11") (name "Net-(D3-C)") (class "Default")
      (node (ref "C21") (pin "2") (pinfunction "2_2") (pintype "passive"))
      (node (ref "C54") (pin "1") (pinfunction "1_1") (pintype "passive"))
      (node (ref "C61") (pin "1") (pinfunction "1_1") (pintype "passive"))
      (node (ref "D3") (pin "1") (pinfunction "C_1") (pintype "passive"))
      (node (ref "IC4") (pin "5") (pinfunction "EN/UVLO_5") (pintype "input"))
      (node (ref "IC4") (pin "8") (pinfunction "VIN_8") (pintype "input"))
      (node (ref "L1") (pin "1") (pinfunction "1_1") (pintype "passive"))
    )
    (net (code "12") (name "Net-(IC5-BOOST)") (class "Default")
      (node (ref "C23") (pin "1") (pinfunction "1_1") (pintype "passive"))
      (node (ref "IC5") (pin "18") (pinfunction "BOOST_18") (pintype "passive"))
    )
    (net (code "13") (name "Net-(IC5-ITH)") (class "Default")
      (node (ref "C26") (pin "2") (pinfunction "2_2") (pintype "passive"))
      (node (ref "IC5") (pin "15") (pinfunction "ITH_15") (pintype "passive"))
      (node (ref "R15") (pin "2") (pinfunction "2_2") (pintype "passive"))
    )
    (net (code "14") (name "Net-(IC5-Iset)") (class "Default")
      (node (ref "C62") (pin "2") (pinfunction "2_2") (pintype "passive"))
      (node (ref "IC5") (pin "14") (pinfunction "Iset_14") (pintype "passive"))
      (node (ref "R20") (pin "2") (pinfunction "2_2") (pintype "passive"))
    )
    (net (code "15") (name "Net-(IC5-MODE{slash}SYNC)") (class "Default")
      (node (ref "IC5") (pin "7") (pinfunction "MODE/SYNC_7") (pintype "input"))
      (node (ref "R18") (pin "2") (pinfunction "2_2") (pintype "passive"))
    )
    (net (code "16") (name "Net-(IC5-PGDFB)") (class "Default")
      (node (ref "IC5") (pin "9") (pinfunction "PGDFB_9") (pintype "input"))
      (node (ref "R16") (pin "2") (pinfunction "2_2") (pintype "passive"))
      (node (ref "R33") (pin "2") (pinfunction "2_2") (pintype "passive"))
    )
    (net (code "17") (name "Net-(IC5-RUN)") (class "Default")
      (node (ref "IC5") (pin "5") (pinfunction "RUN_5") (pintype "input"))
      (node (ref "R14") (pin "1") (pinfunction "1_1") (pintype "passive"))
    )
    (net (code "18") (name "Net-(IC5-Rt)") (class "Default")
      (node (ref "IC5") (pin "12") (pinfunction "Rt_12") (pintype "input"))
      (node (ref "R19") (pin "2") (pinfunction "2_2") (pintype "passive"))
    )
    (net (code "19") (name "Net-(IC12-EN)") (class "Default")
      (node (ref "C57") (pin "2") (pinfunction "2_2") (pintype "passive"))
      (node (ref "C58") (pin "2") (pinfunction "2_2") (pintype "passive"))
      (node (ref "IC12") (pin "2") (pinfunction "VIN_2") (pintype "input"))
      (node (ref "IC12") (pin "3") (pinfunction "EN_3") (pintype "input"))
      (node (ref "L1") (pin "2") (pinfunction "2_2") (pintype "passive"))
    )
    (net (code "20") (name "Net-(IC12-FB)") (class "Default")
      (node (ref "IC12") (pin "5") (pinfunction "FB_5") (pintype "input"))
      (node (ref "R81") (pin "1") (pinfunction "1_1") (pintype "passive"))
      (node (ref "R82") (pin "2") (pinfunction "2_2") (pintype "passive"))
    )
    (net (code "21") (name "Net-(IC12-SW)") (class "Default")
      (node (ref "IC12") (pin "9") (pinfunction "SW_9") (pintype "output"))
      (node (ref "L2") (pin "1") (pinfunction "1_1") (pintype "passive"))
    )
    (net (code "22") (name "Net-(IC16A-IN+)") (class "Default")
      (node (ref "IC16") (pin "5") (pinfunction "IN+_5") (pintype "input"))
      (node (ref "R94") (pin "2") (pinfunction "2_2") (pintype "passive"))
      (node (ref "R95") (pin "1") (pinfunction "1_1") (pintype "passive"))
    )
    (net (code "23") (name "Net-(IC16B-IN+)") (class "Default")
      (node (ref "IC16") (pin "7") (pinfunction "IN+_7") (pintype "input"))
      (node (ref "R96") (pin "1") (pinfunction "1_1") (pintype "passive"))
      (node (ref "R97") (pin "2") (pinfunction "2_2") (pintype "passive"))
    )
    (net (code "24") (name "Net-(IC16C-IN+)") (class "Default")
      (node (ref "IC16") (pin "9") (pinfunction "IN+_9") (pintype "input"))
      (node (ref "R98") (pin "1") (pinfunction "1_1") (pintype "passive"))
      (node (ref "R99") (pin "2") (pinfunction "2_2") (pintype "passive"))
    )
    (net (code "25") (name "Net-(IC16D-IN-)") (class "Default")
      (node (ref "IC16") (pin "10") (pinfunction "IN-_10") (pintype "input"))
      (node (ref "R91") (pin "1") (pinfunction "1_1") (pintype "passive"))
      (node (ref "R93") (pin "1") (pinfunction "1_1") (pintype "passive"))
    )
    (net (code "26") (name "Net-(IC19-EN)") (class "Default")
      (node (ref "IC19") (pin "3") (pinfunction "EN_3") (pintype "input"))
      (node (ref "R28") (pin "1") (pinfunction "1_1") (pintype "passive"))
    )
    (net (code "27") (name "Net-(IC19-FB)") (class "Default")
      (node (ref "C71") (pin "1") (pinfunction "1_1") (pintype "passive"))
      (node (ref "C72") (pin "1") (pinfunction "1_1") (pintype "passive"))
      (node (ref "IC19") (pin "6") (pinfunction "FB_6") (pintype "input"))
      (node (ref "R30") (pin "1") (pinfunction "1_1") (pintype "passive"))
      (node (ref "R31") (pin "2") (pinfunction "2_2") (pintype "passive"))
    )
    (net (code "28") (name "Net-(IC19-RON)") (class "Default")
      (node (ref "IC19") (pin "2") (pinfunction "RON_2") (pintype "input"))
      (node (ref "R27") (pin "1") (pinfunction "1_1") (pintype "passive"))
    )
    (net (code "29") (name "Net-(IC19-SS)") (class "Default")
      (node (ref "C70") (pin "2") (pinfunction "2_2") (pintype "passive"))
      (node (ref "IC19") (pin "5") (pinfunction "SS_5") (pintype "passive"))
    )
    (net (code "30") (name "Net-(LD3-A)") (class "Default")
      (node (ref "LD3") (pin "2") (pinfunction "A_2") (pintype "passive"))
      (node (ref "R21") (pin "2") (pinfunction "2_2") (pintype "passive"))
    )
    (net (code "31") (name "Net-(LD16-A)") (class "Default")
      (node (ref "LD16") (pin "2") (pinfunction "A_2") (pintype "passive"))
      (node (ref "R109") (pin "2") (pinfunction "2_2") (pintype "passive"))
    )
    (net (code "32") (name "Net-(LD17-A)") (class "Default")
      (node (ref "LD17") (pin "2") (pinfunction "A_2") (pintype "passive"))
      (node (ref "R110") (pin "1") (pinfunction "1_1") (pintype "passive"))
    )
    (net (code "33") (name "Net-(LD18-C)") (class "Default")
      (node (ref "LD18") (pin "1") (pinfunction "C_1") (pintype "passive"))
      (node (ref "R108") (pin "2") (pinfunction "2_2") (pintype "passive"))
    )
    (net (code "34") (name "Net-(LD19-A)") (class "Default")
      (node (ref "LD19") (pin "2") (pinfunction "A_2") (pintype "passive"))
      (node (ref "R111") (pin "1") (pinfunction "1_1") (pintype "passive"))
    )
    (net (code "35") (name "Net-(R26-Pad1)") (class "Default")
      (node (ref "R26") (pin "1") (pinfunction "1_1") (pintype "passive"))
      (node (ref "R27") (pin "2") (pinfunction "2_2") (pintype "passive"))
    )
    (net (code "36") (name "P3V3") (class "Default")
      (node (ref "C55") (pin "2") (pinfunction "2_2") (pintype "passive"))
      (node (ref "C56") (pin "2") (pinfunction "2_2") (pintype "passive"))
      (node (ref "IC12") (pin "10") (pinfunction "VOS_10") (pintype "input"))
      (node (ref "IC12") (pin "8") (pinfunction "SLEEP_8") (pintype "input"))
      (node (ref "IC16") (pin "3") (pinfunction "V+_3") (pintype "power_in"))
      (node (ref "L2") (pin "2") (pinfunction "2_2") (pintype "passive"))
      (node (ref "R100") (pin "2") (pinfunction "2_2") (pintype "passive"))
      (node (ref "R111") (pin "2") (pinfunction "2_2") (pintype "passive"))
      (node (ref "R14") (pin "2") (pinfunction "2_2") (pintype "passive"))
      (node (ref "R25") (pin "1") (pinfunction "1_1") (pintype "passive"))
      (node (ref "R81") (pin "2") (pinfunction "2_2") (pintype "passive"))
      (node (ref "R92") (pin "1") (pinfunction "1_1") (pintype "passive"))
      (node (ref "R94") (pin "1") (pinfunction "1_1") (pintype "passive"))
    )
    (net (code "37") (name "P5V0") (class "Default")
      (node (ref "C22") (pin "2") (pinfunction "2_2") (pintype "passive"))
      (node (ref "IC4") (pin "1") (pinfunction "VOUT_1") (pintype "power_in"))
      (node (ref "IC4") (pin "2") (pinfunction "SENS_2") (pintype "input"))
      (node (ref "R21") (pin "1") (pinfunction "1_1") (pintype "passive"))
    )
    (net (code "38") (name "P6V5") (class "Default")
      (node (ref "C68") (pin "2") (pinfunction "2_2") (pintype "passive"))
      (node (ref "C69") (pin "2") (pinfunction "2_2") (pintype "passive"))
      (node (ref "C71") (pin "2") (pinfunction "2_2") (pintype "passive"))
      (node (ref "C72") (pin "2") (pinfunction "2_2") (pintype "passive"))
      (node (ref "D3") (pin "2") (pinfunction "A_2") (pintype "passive"))
      (node (ref "IC19") (pin "7") (pinfunction "VOUT_7") (pintype "power_in"))
      (node (ref "R109") (pin "1") (pinfunction "1_1") (pintype "passive"))
      (node (ref "R30") (pin "2") (pinfunction "2_2") (pintype "passive"))
      (node (ref "R98") (pin "2") (pinfunction "2_2") (pintype "passive"))
    )
    (net (code "39") (name "P12V0") (class "Default")
      (node (ref "C24") (pin "2") (pinfunction "2_2") (pintype "passive"))
      (node (ref "C25") (pin "2") (pinfunction "2_2") (pintype "passive"))
      (node (ref "C59") (pin "1") (pinfunction "1_1") (pintype "passive"))
      (node (ref "C64") (pin "2") (pinfunction "2_2") (pintype "passive"))
      (node (ref "C66") (pin "2") (pinfunction "2_2") (pintype "passive"))
      (node (ref "C67") (pin "2") (pinfunction "2_2") (pintype "passive"))
      (node (ref "IC19") (pin "1") (pinfunction "VIN_1") (pintype "input"))
      (node (ref "IC5") (pin "3") (pinfunction "Vin_3") (pintype "power_in"))
      (node (ref "IC5") (pin "4") (pinfunction "Vin_4") (pintype "power_in"))
      (node (ref "J3") (pin "3") (pinfunction "3_3") (pintype "bidirectional"))
      (node (ref "R26") (pin "2") (pinfunction "2_2") (pintype "passive"))
      (node (ref "R28") (pin "2") (pinfunction "2_2") (pintype "passive"))
    )
    (net (code "40") (name "P30V0") (class "Default")
      (node (ref "C63") (pin "2") (pinfunction "2_2") (pintype "passive"))
      (node (ref "L4") (pin "2") (pinfunction "2_2") (pintype "passive"))
      (node (ref "R110") (pin "2") (pinfunction "2_2") (pintype "passive"))
      (node (ref "R96") (pin "2") (pinfunction "2_2") (pintype "passive"))
    )
    (net (code "41") (name "unconnected-(IC4-NC-Pad4)") (class "Default")
      (node (ref "IC4") (pin "4") (pinfunction "NC_4") (pintype "passive"))
    )
    (net (code "42") (name "unconnected-(IC4-PG-Pad7)") (class "Default")
      (node (ref "IC4") (pin "7") (pinfunction "PG_7") (pintype "output"))
    )
    (net (code "43") (name "unconnected-(IC12-NC-Pad4)") (class "Default")
      (node (ref "IC12") (pin "4") (pinfunction "NC_4") (pintype "passive"))
    )
    (net (code "44") (name "unconnected-(IC12-PG-Pad7)") (class "Default")
      (node (ref "IC12") (pin "7") (pinfunction "PG_7") (pintype "output"))
    )
  )
)
